# Band-Pass_Filter.net
KiCad netlist of a schematic drawn in Altium Designer
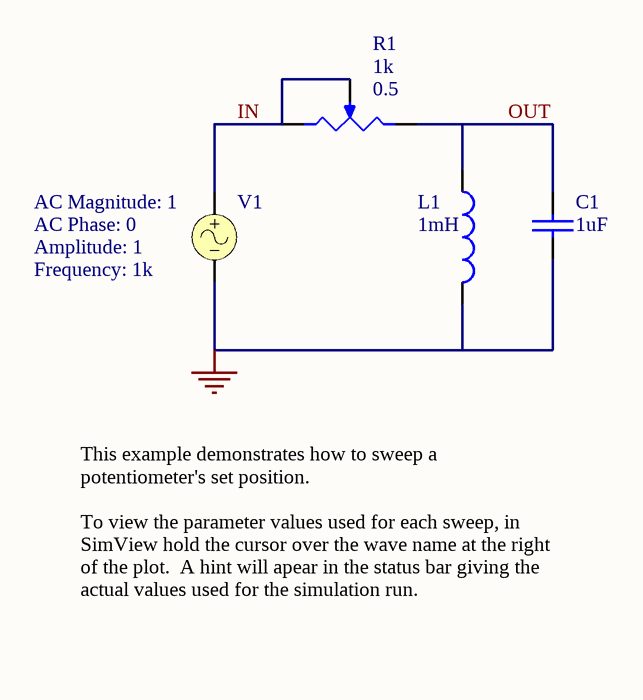
[diagram p0: Band-Pass Filter.SchDoc]

(export (version "E")
  (design (tool "Eeschema 10.0.6"))
  (components
    (comp (ref "C1")
      (value "1uF")
      (description "Capacitor")
      (fields (field (name "Comment") "CAP"))
      (libsource (lib "Generic General Devices") (part "CAP"))
    )
    (comp (ref "L1")
      (value "1mH")
      (description "Inductor")
      (fields (field (name "Comment") "INDUCTOR"))
      (libsource (lib "altium-import") (part "root_0_INDUCTOR_"))
    )
    (comp (ref "R1")
      (value "1k")
      (description "Potentiometer")
      (fields (field (name "SET POSITION") "0.5") (field (name "Comment") "RPOT"))
      (libsource (lib "altium-import") (part "root_3_RPOT_"))
    )
    (comp (ref "V1")
      (value "VSIN")
      (description "Sinusoidal Voltage Source")
      (fields
        (field (name "AC MAGNITUDE") "1")
        (field (name "AC PHASE") "0")
        (field (name "AMPLITUDE") "1")
        (field (name "FREQUENCY") "1k")
      )
      (libsource (lib "altium-import") (part "root_0_VSIN_"))
    )
  )
  (nets
    (net (code "1") (name "/IN") (class "Default")
      (node (ref "R1") (pin "2") (pinfunction "BOT_2") (pintype "passive"))
      (node (ref "R1") (pin "3") (pinfunction "TAP_3") (pintype "passive"))
      (node (ref "V1") (pin "1") (pinfunction "1_1") (pintype "passive"))
    )
    (net (code "2") (name "/OUT") (class "Default")
      (node (ref "C1") (pin "1") (pinfunction "1_1") (pintype "passive"))
      (node (ref "L1") (pin "1") (pinfunction "1_1") (pintype "passive"))
      (node (ref "R1") (pin "1") (pinfunction "TOP_1") (pintype "passive"))
    )
    (net (code "3") (name "GND") (class "Default")
      (node (ref "C1") (pin "2") (pinfunction "2_2") (pintype "passive"))
      (node (ref "L1") (pin "2") (pinfunction "2_2") (pintype "passive"))
      (node (ref "V1") (pin "2") (pinfunction "2_2") (pintype "passive"))
    )
  )
)
